# Power.net
KiCad netlist of a schematic drawn in Altium Designer
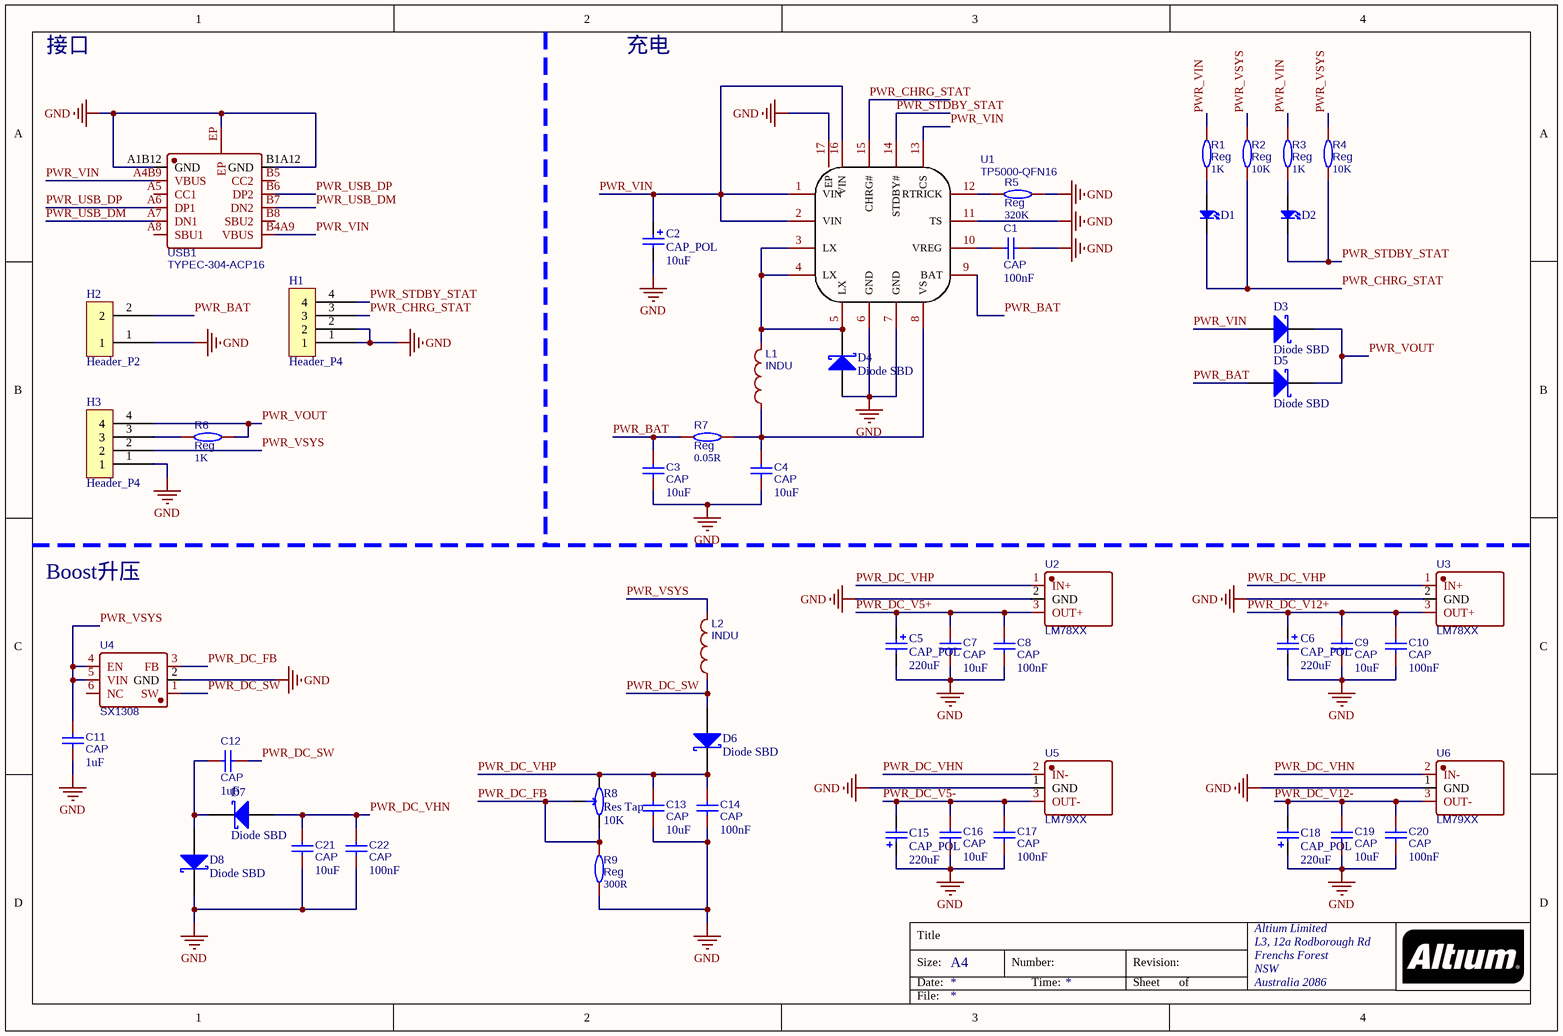
[diagram p0: Power.SchDoc]

(export (version "E")
  (design (tool "Eeschema 10.0.6"))
  (components
    (comp (ref "C1")
      (value "CAP")
      (footprint "C0603")
      (description "Cap")
      (fields
        (field (name "BOM_SUPPLIER PART") "C302008")
        (field (name "BOM_MANUFACTURER PART") "0603B103K101CT")
        (field (name "ALTIUM_VALUE") "100nF")
        (field (name "CONTRIBUTOR") "LCSC")
      )
      (libsource (lib "Levent_lib") (part "CAP"))
    )
    (comp (ref "C2")
      (value "CAP_POL")
      (footprint "CP1206")
      (description "极性电容")
      (fields (field (name "ALTIUM_VALUE") "10uF"))
      (libsource (lib "Levent_lib") (part "CAP_POL"))
    )
    (comp (ref "C3")
      (value "CAP")
      (footprint "C0603")
      (description "Cap")
      (fields
        (field (name "BOM_SUPPLIER PART") "C302008")
        (field (name "BOM_MANUFACTURER PART") "0603B103K101CT")
        (field (name "ALTIUM_VALUE") "10uF")
        (field (name "CONTRIBUTOR") "LCSC")
      )
      (libsource (lib "Levent_lib") (part "CAP"))
    )
    (comp (ref "C4")
      (value "CAP")
      (footprint "C0603")
      (description "Cap")
      (fields
        (field (name "BOM_SUPPLIER PART") "C302008")
        (field (name "BOM_MANUFACTURER PART") "0603B103K101CT")
        (field (name "ALTIUM_VALUE") "10uF")
        (field (name "CONTRIBUTOR") "LCSC")
      )
      (libsource (lib "Levent_lib") (part "CAP"))
    )
    (comp (ref "C5")
      (value "CAP_POL")
      (footprint "CAP_SMD_6.3mm")
      (description "极性电容")
      (fields (field (name "ALTIUM_VALUE") "220uF"))
      (libsource (lib "Levent_lib") (part "CAP_POL"))
    )
    (comp (ref "C6")
      (value "CAP_POL")
      (footprint "CAP_SMD_6.3mm")
      (description "极性电容")
      (fields (field (name "ALTIUM_VALUE") "220uF"))
      (libsource (lib "Levent_lib") (part "CAP_POL"))
    )
    (comp (ref "C7")
      (value "CAP")
      (footprint "C0603")
      (description "Cap")
      (fields
        (field (name "BOM_SUPPLIER PART") "C302008")
        (field (name "BOM_MANUFACTURER PART") "0603B103K101CT")
        (field (name "ALTIUM_VALUE") "10uF")
        (field (name "CONTRIBUTOR") "LCSC")
      )
      (libsource (lib "Levent_lib") (part "CAP"))
    )
    (comp (ref "C8")
      (value "CAP")
      (footprint "C0603")
      (description "Cap")
      (fields
        (field (name "BOM_SUPPLIER PART") "C302008")
        (field (name "BOM_MANUFACTURER PART") "0603B103K101CT")
        (field (name "ALTIUM_VALUE") "100nF")
        (field (name "CONTRIBUTOR") "LCSC")
      )
      (libsource (lib "Levent_lib") (part "CAP"))
    )
    (comp (ref "C9")
      (value "CAP")
      (footprint "C0603")
      (description "Cap")
      (fields
        (field (name "BOM_SUPPLIER PART") "C302008")
        (field (name "BOM_MANUFACTURER PART") "0603B103K101CT")
        (field (name "ALTIUM_VALUE") "10uF")
        (field (name "CONTRIBUTOR") "LCSC")
      )
      (libsource (lib "Levent_lib") (part "CAP"))
    )
    (comp (ref "C10")
      (value "CAP")
      (footprint "C0603")
      (description "Cap")
      (fields
        (field (name "BOM_SUPPLIER PART") "C302008")
        (field (name "BOM_MANUFACTURER PART") "0603B103K101CT")
        (field (name "ALTIUM_VALUE") "100nF")
        (field (name "CONTRIBUTOR") "LCSC")
      )
      (libsource (lib "Levent_lib") (part "CAP"))
    )
    (comp (ref "C11")
      (value "CAP")
      (footprint "C0603")
      (description "Cap")
      (fields
        (field (name "BOM_SUPPLIER PART") "C302008")
        (field (name "BOM_MANUFACTURER PART") "0603B103K101CT")
        (field (name "ALTIUM_VALUE") "1uF")
        (field (name "CONTRIBUTOR") "LCSC")
      )
      (libsource (lib "Levent_lib") (part "CAP"))
    )
    (comp (ref "C12")
      (value "CAP")
      (footprint "C0603")
      (description "Cap")
      (fields
        (field (name "BOM_SUPPLIER PART") "C302008")
        (field (name "BOM_MANUFACTURER PART") "0603B103K101CT")
        (field (name "ALTIUM_VALUE") "1uF")
        (field (name "CONTRIBUTOR") "LCSC")
      )
      (libsource (lib "Levent_lib") (part "CAP"))
    )
    (comp (ref "C13")
      (value "CAP")
      (footprint "C0603")
      (description "Cap")
      (fields
        (field (name "BOM_SUPPLIER PART") "C302008")
        (field (name "BOM_MANUFACTURER PART") "0603B103K101CT")
        (field (name "ALTIUM_VALUE") "10uF")
        (field (name "CONTRIBUTOR") "LCSC")
      )
      (libsource (lib "Levent_lib") (part "CAP"))
    )
    (comp (ref "C14")
      (value "CAP")
      (footprint "C0603")
      (description "Cap")
      (fields
        (field (name "BOM_SUPPLIER PART") "C302008")
        (field (name "BOM_MANUFACTURER PART") "0603B103K101CT")
        (field (name "ALTIUM_VALUE") "100nF")
        (field (name "CONTRIBUTOR") "LCSC")
      )
      (libsource (lib "Levent_lib") (part "CAP"))
    )
    (comp (ref "C15")
      (value "CAP_POL")
      (footprint "CAP_SMD_6.3mm")
      (description "极性电容")
      (fields (field (name "ALTIUM_VALUE") "220uF"))
      (libsource (lib "Levent_lib") (part "CAP_POL"))
    )
    (comp (ref "C16")
      (value "CAP")
      (footprint "C0603")
      (description "Cap")
      (fields
        (field (name "BOM_SUPPLIER PART") "C302008")
        (field (name "BOM_MANUFACTURER PART") "0603B103K101CT")
        (field (name "ALTIUM_VALUE") "10uF")
        (field (name "CONTRIBUTOR") "LCSC")
      )
      (libsource (lib "Levent_lib") (part "CAP"))
    )
    (comp (ref "C17")
      (value "CAP")
      (footprint "C0603")
      (description "Cap")
      (fields
        (field (name "BOM_SUPPLIER PART") "C302008")
        (field (name "BOM_MANUFACTURER PART") "0603B103K101CT")
        (field (name "ALTIUM_VALUE") "100nF")
        (field (name "CONTRIBUTOR") "LCSC")
      )
      (libsource (lib "Levent_lib") (part "CAP"))
    )
    (comp (ref "C18")
      (value "CAP_POL")
      (footprint "CAP_SMD_6.3mm")
      (description "极性电容")
      (fields (field (name "ALTIUM_VALUE") "220uF"))
      (libsource (lib "Levent_lib") (part "CAP_POL"))
    )
    (comp (ref "C19")
      (value "CAP")
      (footprint "C0603")
      (description "Cap")
      (fields
        (field (name "BOM_SUPPLIER PART") "C302008")
        (field (name "BOM_MANUFACTURER PART") "0603B103K101CT")
        (field (name "ALTIUM_VALUE") "10uF")
        (field (name "CONTRIBUTOR") "LCSC")
      )
      (libsource (lib "Levent_lib") (part "CAP"))
    )
    (comp (ref "C20")
      (value "CAP")
      (footprint "C0603")
      (description "Cap")
      (fields
        (field (name "BOM_SUPPLIER PART") "C302008")
        (field (name "BOM_MANUFACTURER PART") "0603B103K101CT")
        (field (name "ALTIUM_VALUE") "100nF")
        (field (name "CONTRIBUTOR") "LCSC")
      )
      (libsource (lib "Levent_lib") (part "CAP"))
    )
    (comp (ref "C21")
      (value "CAP")
      (footprint "C0603")
      (description "Cap")
      (fields
        (field (name "BOM_SUPPLIER PART") "C302008")
        (field (name "BOM_MANUFACTURER PART") "0603B103K101CT")
        (field (name "ALTIUM_VALUE") "10uF")
        (field (name "CONTRIBUTOR") "LCSC")
      )
      (libsource (lib "Levent_lib") (part "CAP"))
    )
    (comp (ref "C22")
      (value "CAP")
      (footprint "C0603")
      (description "Cap")
      (fields
        (field (name "BOM_SUPPLIER PART") "C302008")
        (field (name "BOM_MANUFACTURER PART") "0603B103K101CT")
        (field (name "ALTIUM_VALUE") "100nF")
        (field (name "CONTRIBUTOR") "LCSC")
      )
      (libsource (lib "Levent_lib") (part "CAP"))
    )
    (comp (ref "D1")
      (value "LED")
      (footprint "LED0603_Side")
      (fields (field (name "PUBLISHER") "Altium Limited"))
      (libsource (lib "Levent_lib") (part "LED0"))
    )
    (comp (ref "D2")
      (value "LED")
      (footprint "LED0603_Side")
      (fields (field (name "PUBLISHER") "Altium Limited"))
      (libsource (lib "Levent_lib") (part "LED0"))
    )
    (comp (ref "D3")
      (value "Diode SBD")
      (footprint "SMA_L4.3")
      (description "Schottky Rectifier")
      (fields (field (name "PUBLISHER") "Altium Limited"))
      (libsource (lib "Levent_lib") (part "Diode SBD"))
    )
    (comp (ref "D4")
      (value "Diode SBD")
      (footprint "SMA_L4.3")
      (description "Schottky Rectifier")
      (fields (field (name "PUBLISHER") "Altium Limited"))
      (libsource (lib "Levent_lib") (part "Diode SBD"))
    )
    (comp (ref "D5")
      (value "Diode SBD")
      (footprint "SMA_L4.3")
      (description "Schottky Rectifier")
      (fields (field (name "PUBLISHER") "Altium Limited"))
      (libsource (lib "Levent_lib") (part "Diode SBD"))
    )
    (comp (ref "D6")
      (value "Diode SBD")
      (footprint "SMA_L4.3")
      (description "Schottky Rectifier")
      (fields (field (name "PUBLISHER") "Altium Limited"))
      (libsource (lib "Levent_lib") (part "Diode SBD"))
    )
    (comp (ref "D7")
      (value "Diode SBD")
      (footprint "SMA_L4.3")
      (description "Schottky Rectifier")
      (fields (field (name "PUBLISHER") "Altium Limited"))
      (libsource (lib "Levent_lib") (part "Diode SBD"))
    )
    (comp (ref "D8")
      (value "Diode SBD")
      (footprint "SMA_L4.3")
      (description "Schottky Rectifier")
      (fields (field (name "PUBLISHER") "Altium Limited"))
      (libsource (lib "Levent_lib") (part "Diode SBD"))
    )
    (comp (ref "H1")
      (value "Header_P4")
      (footprint "PH_4Pin")
      (description "4Pin排针")
      (libsource (lib "Levent_lib") (part "Header_P4"))
    )
    (comp (ref "H2")
      (value "Header_P2")
      (footprint "XH_2Pin")
      (description "2Pin排针")
      (libsource (lib "Levent_lib") (part "Header_P2"))
    )
    (comp (ref "H3")
      (value "Header_P4")
      (footprint "PH_4Pin")
      (description "4Pin排针")
      (libsource (lib "Levent_lib") (part "Header_P4"))
    )
    (comp (ref "L1")
      (value "INDU")
      (footprint "SMD_L7.1")
      (description "电感")
      (fields
        (field (name "BOM_SUPPLIER PART") "C182182")
        (field (name "BOM_MANUFACTURER PART") "SLO0630H150MTT")
        (field (name "CONTRIBUTOR") "LCSC")
      )
      (libsource (lib "Levent_lib") (part "IND"))
    )
    (comp (ref "L2")
      (value "INDU")
      (footprint "SMD_L7.1")
      (description "电感")
      (fields
        (field (name "BOM_SUPPLIER PART") "C182182")
        (field (name "BOM_MANUFACTURER PART") "SLO0630H150MTT")
        (field (name "CONTRIBUTOR") "LCSC")
      )
      (libsource (lib "Levent_lib") (part "IND"))
    )
    (comp (ref "R1")
      (value "Reg")
      (footprint "R0603")
      (description "电阻")
      (fields
        (field (name "BOM_SUPPLIER PART") "C465721")
        (field (name "BOM_MANUFACTURER PART") "AR03BTCX1002A")
        (field (name "ALTIUM_VALUE") "1K")
        (field (name "CONTRIBUTOR") "LCSC")
      )
      (libsource (lib "Levent_lib") (part "Res"))
    )
    (comp (ref "R2")
      (value "Reg")
      (footprint "R0603")
      (description "电阻")
      (fields
        (field (name "BOM_SUPPLIER PART") "C465721")
        (field (name "BOM_MANUFACTURER PART") "AR03BTCX1002A")
        (field (name "ALTIUM_VALUE") "10K")
        (field (name "CONTRIBUTOR") "LCSC")
      )
      (libsource (lib "Levent_lib") (part "Res"))
    )
    (comp (ref "R3")
      (value "Reg")
      (footprint "R0603")
      (description "电阻")
      (fields
        (field (name "BOM_SUPPLIER PART") "C465721")
        (field (name "BOM_MANUFACTURER PART") "AR03BTCX1002A")
        (field (name "ALTIUM_VALUE") "1K")
        (field (name "CONTRIBUTOR") "LCSC")
      )
      (libsource (lib "Levent_lib") (part "Res"))
    )
    (comp (ref "R4")
      (value "Reg")
      (footprint "R0603")
      (description "电阻")
      (fields
        (field (name "BOM_SUPPLIER PART") "C465721")
        (field (name "BOM_MANUFACTURER PART") "AR03BTCX1002A")
        (field (name "ALTIUM_VALUE") "10K")
        (field (name "CONTRIBUTOR") "LCSC")
      )
      (libsource (lib "Levent_lib") (part "Res"))
    )
    (comp (ref "R5")
      (value "Reg")
      (footprint "R0603")
      (description "电阻")
      (fields
        (field (name "BOM_SUPPLIER PART") "C465721")
        (field (name "BOM_MANUFACTURER PART") "AR03BTCX1002A")
        (field (name "ALTIUM_VALUE") "320K")
        (field (name "CONTRIBUTOR") "LCSC")
      )
      (libsource (lib "Levent_lib") (part "Res"))
    )
    (comp (ref "R6")
      (value "Reg")
      (footprint "R0603")
      (description "电阻")
      (fields
        (field (name "BOM_SUPPLIER PART") "C465721")
        (field (name "BOM_MANUFACTURER PART") "AR03BTCX1002A")
        (field (name "ALTIUM_VALUE") "1K")
        (field (name "CONTRIBUTOR") "LCSC")
      )
      (libsource (lib "Levent_lib") (part "Res"))
    )
    (comp (ref "R7")
      (value "Reg")
      (footprint "R2512")
      (description "电阻")
      (fields
        (field (name "BOM_SUPPLIER PART") "C465721")
        (field (name "BOM_MANUFACTURER PART") "AR03BTCX1002A")
        (field (name "ALTIUM_VALUE") "0.05R")
        (field (name "CONTRIBUTOR") "LCSC")
      )
      (libsource (lib "Levent_lib") (part "Res"))
    )
    (comp (ref "R8")
      (value "Res Tap")
      (footprint "RES_TAP_HOR")
      (description "可调电阻")
      (fields (field (name "ALTIUM_VALUE") "10K") (field (name "PUBLISHER") "Altium Limited"))
      (libsource (lib "Levent_lib") (part "Res Tap"))
    )
    (comp (ref "R9")
      (value "Reg")
      (footprint "R0603")
      (description "电阻")
      (fields
        (field (name "BOM_SUPPLIER PART") "C465721")
        (field (name "BOM_MANUFACTURER PART") "AR03BTCX1002A")
        (field (name "ALTIUM_VALUE") "300R")
        (field (name "CONTRIBUTOR") "LCSC")
      )
      (libsource (lib "Levent_lib") (part "Res"))
    )
    (comp (ref "U1")
      (value "TP5000-QFN16")
      (footprint "QFN-16_L4.0-W4.0-P0.65-BL-EP2.2")
      (fields (field (name "BOM_SUPPLIER PART") "C51699"))
      (libsource (lib "Levent_lib") (part "TP5000-QFN16"))
    )
    (comp (ref "U2")
      (value "LM78XX")
      (footprint "TO-220-3_2.54_HOR")
      (description "三端稳压(正电压)")
      (fields
        (field (name "BOM_SUPPLIER PART") "C2902509")
        (field (name "BOM_MANUFACTURER PART") "LM7812T")
        (field (name "CONTRIBUTOR") "LCSC")
      )
      (libsource (lib "Levent_lib") (part "LM78XX"))
    )
    (comp (ref "U3")
      (value "LM78XX")
      (footprint "TO-220-3_2.54_HOR")
      (description "三端稳压(正电压)")
      (fields
        (field (name "BOM_SUPPLIER PART") "C2902509")
        (field (name "BOM_MANUFACTURER PART") "LM7812T")
        (field (name "CONTRIBUTOR") "LCSC")
      )
      (libsource (lib "Levent_lib") (part "LM78XX"))
    )
    (comp (ref "U4")
      (value "SX1308")
      (footprint "SOT-23-6")
      (description "升压PWM")
      (fields (field (name "BOM_SUPPLIER PART") "C78162"))
      (libsource (lib "Levent_lib") (part "SX1308"))
    )
    (comp (ref "U5")
      (value "LM79XX")
      (footprint "TO-220-3_2.54_HOR")
      (description "三端稳压(负电压)")
      (fields
        (field (name "BOM_SUPPLIER PART") "C2902509")
        (field (name "BOM_MANUFACTURER PART") "LM7812T")
        (field (name "CONTRIBUTOR") "LCSC")
      )
      (libsource (lib "Levent_lib_commons") (part "LM79XX"))
    )
    (comp (ref "U6")
      (value "LM79XX")
      (footprint "TO-220-3_2.54_HOR")
      (description "三端稳压(负电压)")
      (fields
        (field (name "BOM_SUPPLIER PART") "C2902509")
        (field (name "BOM_MANUFACTURER PART") "LM7812T")
        (field (name "CONTRIBUTOR") "LCSC")
      )
      (libsource (lib "Levent_lib_commons") (part "LM79XX"))
    )
    (comp (ref "USB1")
      (value "TYPEC-304-ACP16")
      (footprint "USB-C-SMD_TYPE-C-16P")
      (description "全引脚USB TYPEC母座")
      (fields (field (name "BOM_SUPPLIER PART") "C2982555") (field (name "CONTRIBUTOR") "LCSC"))
      (libsource (lib "Levent_lib") (part "USB_TYPEC_12P"))
    )
  )
  (nets
    (net (code "1") (name "/PWR_BAT") (class "Default")
      (node (ref "C3") (pin "1") (pinfunction "1_1") (pintype "passive"))
      (node (ref "D5") (pin "2") (pinfunction "A_2") (pintype "passive"))
      (node (ref "H2") (pin "2") (pinfunction "2_2") (pintype "passive"))
      (node (ref "R7") (pin "1") (pinfunction "1_1") (pintype "passive"))
      (node (ref "U1") (pin "9") (pinfunction "BAT_9") (pintype "passive"))
    )
    (net (code "2") (name "/PWR_CHRG_STAT") (class "Default")
      (node (ref "D1") (pin "1") (pinfunction "K_1") (pintype "passive"))
      (node (ref "H1") (pin "3") (pinfunction "3_3") (pintype "passive"))
      (node (ref "R2") (pin "1") (pinfunction "1_1") (pintype "passive"))
      (node (ref "U1") (pin "15") (pinfunction "CHRG#_15") (pintype "passive"))
    )
    (net (code "3") (name "/PWR_DC_FB") (class "Default")
      (node (ref "R8") (pin "1") (pinfunction "A_1") (pintype "passive"))
      (node (ref "R8") (pin "3") (pinfunction "TAP_3") (pintype "passive"))
      (node (ref "R9") (pin "2") (pinfunction "2_2") (pintype "passive"))
      (node (ref "U4") (pin "3") (pinfunction "FB_3") (pintype "passive"))
    )
    (net (code "4") (name "/PWR_DC_SW") (class "Default")
      (node (ref "C12") (pin "1") (pinfunction "1_1") (pintype "passive"))
      (node (ref "D6") (pin "2") (pinfunction "A_2") (pintype "passive"))
      (node (ref "L2") (pin "1") (pinfunction "1_1") (pintype "passive"))
      (node (ref "U4") (pin "1") (pinfunction "SW_1") (pintype "passive"))
    )
    (net (code "5") (name "/PWR_DC_V5+") (class "Default")
      (node (ref "C5") (pin "1") (pinfunction "1_1") (pintype "passive"))
      (node (ref "C7") (pin "1") (pinfunction "1_1") (pintype "passive"))
      (node (ref "C8") (pin "1") (pinfunction "1_1") (pintype "passive"))
      (node (ref "U2") (pin "3") (pinfunction "OUT+_3") (pintype "passive"))
    )
    (net (code "6") (name "/PWR_DC_V5-") (class "Default")
      (node (ref "C15") (pin "2") (pinfunction "2_2") (pintype "passive"))
      (node (ref "C16") (pin "1") (pinfunction "1_1") (pintype "passive"))
      (node (ref "C17") (pin "1") (pinfunction "1_1") (pintype "passive"))
      (node (ref "U5") (pin "3") (pinfunction "OUT-_3") (pintype "passive"))
    )
    (net (code "7") (name "/PWR_DC_V12+") (class "Default")
      (node (ref "C10") (pin "1") (pinfunction "1_1") (pintype "passive"))
      (node (ref "C6") (pin "1") (pinfunction "1_1") (pintype "passive"))
      (node (ref "C9") (pin "1") (pinfunction "1_1") (pintype "passive"))
      (node (ref "U3") (pin "3") (pinfunction "OUT+_3") (pintype "passive"))
    )
    (net (code "8") (name "/PWR_DC_V12-") (class "Default")
      (node (ref "C18") (pin "2") (pinfunction "2_2") (pintype "passive"))
      (node (ref "C19") (pin "1") (pinfunction "1_1") (pintype "passive"))
      (node (ref "C20") (pin "1") (pinfunction "1_1") (pintype "passive"))
      (node (ref "U6") (pin "3") (pinfunction "OUT-_3") (pintype "passive"))
    )
    (net (code "9") (name "/PWR_DC_VHN") (class "Default")
      (node (ref "C21") (pin "1") (pinfunction "1_1") (pintype "passive"))
      (node (ref "C22") (pin "1") (pinfunction "1_1") (pintype "passive"))
      (node (ref "D7") (pin "2") (pinfunction "A_2") (pintype "passive"))
      (node (ref "U5") (pin "2") (pinfunction "IN-_2") (pintype "passive"))
      (node (ref "U6") (pin "2") (pinfunction "IN-_2") (pintype "passive"))
    )
    (net (code "10") (name "/PWR_DC_VHP") (class "Default")
      (node (ref "C13") (pin "1") (pinfunction "1_1") (pintype "passive"))
      (node (ref "C14") (pin "1") (pinfunction "1_1") (pintype "passive"))
      (node (ref "D6") (pin "1") (pinfunction "K_1") (pintype "passive"))
      (node (ref "R8") (pin "2") (pinfunction "B_2") (pintype "passive"))
      (node (ref "U2") (pin "1") (pinfunction "IN+_1") (pintype "passive"))
      (node (ref "U3") (pin "1") (pinfunction "IN+_1") (pintype "passive"))
    )
    (net (code "11") (name "/PWR_STDBY_STAT") (class "Default")
      (node (ref "D2") (pin "1") (pinfunction "K_1") (pintype "passive"))
      (node (ref "H1") (pin "4") (pinfunction "4_4") (pintype "passive"))
      (node (ref "R4") (pin "1") (pinfunction "1_1") (pintype "passive"))
      (node (ref "U1") (pin "14") (pinfunction "STDBY#_14") (pintype "passive"))
    )
    (net (code "12") (name "/PWR_USB_DM") (class "Default")
      (node (ref "USB1") (pin "A7") (pinfunction "DN1_A7") (pintype "passive"))
      (node (ref "USB1") (pin "B7") (pinfunction "DN2_B7") (pintype "passive"))
    )
    (net (code "13") (name "/PWR_USB_DP") (class "Default")
      (node (ref "USB1") (pin "A6") (pinfunction "DP1_A6") (pintype "passive"))
      (node (ref "USB1") (pin "B6") (pinfunction "DP2_B6") (pintype "passive"))
    )
    (net (code "14") (name "/PWR_VIN") (class "Default")
      (node (ref "C2") (pin "1") (pinfunction "1_1") (pintype "passive"))
      (node (ref "D3") (pin "2") (pinfunction "A_2") (pintype "passive"))
      (node (ref "R1") (pin "2") (pinfunction "2_2") (pintype "passive"))
      (node (ref "R3") (pin "2") (pinfunction "2_2") (pintype "passive"))
      (node (ref "U1") (pin "1") (pinfunction "VIN_1") (pintype "passive"))
      (node (ref "U1") (pin "13") (pinfunction "CS_13") (pintype "passive"))
      (node (ref "U1") (pin "16") (pinfunction "VIN_16") (pintype "passive"))
      (node (ref "U1") (pin "2") (pinfunction "VIN_2") (pintype "passive"))
      (node (ref "USB1") (pin "A4B9") (pinfunction "VBUS_A4B9") (pintype "passive"))
      (node (ref "USB1") (pin "B4A9") (pinfunction "VBUS_B4A9") (pintype "passive"))
    )
    (net (code "15") (name "/PWR_VOUT") (class "Default")
      (node (ref "D3") (pin "1") (pinfunction "K_1") (pintype "passive"))
      (node (ref "D5") (pin "1") (pinfunction "K_1") (pintype "passive"))
      (node (ref "H3") (pin "4") (pinfunction "4_4") (pintype "passive"))
      (node (ref "R6") (pin "1") (pinfunction "1_1") (pintype "passive"))
    )
    (net (code "16") (name "/PWR_VSYS") (class "Default")
      (node (ref "C11") (pin "1") (pinfunction "1_1") (pintype "passive"))
      (node (ref "H3") (pin "2") (pinfunction "2_2") (pintype "passive"))
      (node (ref "L2") (pin "2") (pinfunction "2_2") (pintype "passive"))
      (node (ref "R2") (pin "2") (pinfunction "2_2") (pintype "passive"))
      (node (ref "R4") (pin "2") (pinfunction "2_2") (pintype "passive"))
      (node (ref "U4") (pin "4") (pinfunction "EN_4") (pintype "passive"))
      (node (ref "U4") (pin "5") (pinfunction "VIN_5") (pintype "passive"))
    )
    (net (code "17") (name "GND") (class "Default")
      (node (ref "C1") (pin "2") (pinfunction "2_2") (pintype "passive"))
      (node (ref "C10") (pin "2") (pinfunction "2_2") (pintype "passive"))
      (node (ref "C11") (pin "2") (pinfunction "2_2") (pintype "passive"))
      (node (ref "C13") (pin "2") (pinfunction "2_2") (pintype "passive"))
      (node (ref "C14") (pin "2") (pinfunction "2_2") (pintype "passive"))
      (node (ref "C15") (pin "1") (pinfunction "1_1") (pintype "passive"))
      (node (ref "C16") (pin "2") (pinfunction "2_2") (pintype "passive"))
      (node (ref "C17") (pin "2") (pinfunction "2_2") (pintype "passive"))
      (node (ref "C18") (pin "1") (pinfunction "1_1") (pintype "passive"))
      (node (ref "C19") (pin "2") (pinfunction "2_2") (pintype "passive"))
      (node (ref "C2") (pin "2") (pinfunction "2_2") (pintype "passive"))
      (node (ref "C20") (pin "2") (pinfunction "2_2") (pintype "passive"))
      (node (ref "C21") (pin "2") (pinfunction "2_2") (pintype "passive"))
      (node (ref "C22") (pin "2") (pinfunction "2_2") (pintype "passive"))
      (node (ref "C3") (pin "2") (pinfunction "2_2") (pintype "passive"))
      (node (ref "C4") (pin "2") (pinfunction "2_2") (pintype "passive"))
      (node (ref "C5") (pin "2") (pinfunction "2_2") (pintype "passive"))
      (node (ref "C6") (pin "2") (pinfunction "2_2") (pintype "passive"))
      (node (ref "C7") (pin "2") (pinfunction "2_2") (pintype "passive"))
      (node (ref "C8") (pin "2") (pinfunction "2_2") (pintype "passive"))
      (node (ref "C9") (pin "2") (pinfunction "2_2") (pintype "passive"))
      (node (ref "D4") (pin "2") (pinfunction "A_2") (pintype "passive"))
      (node (ref "D8") (pin "1") (pinfunction "K_1") (pintype "passive"))
      (node (ref "H1") (pin "1") (pinfunction "1_1") (pintype "passive"))
      (node (ref "H1") (pin "2") (pinfunction "2_2") (pintype "passive"))
      (node (ref "H2") (pin "1") (pinfunction "1_1") (pintype "passive"))
      (node (ref "H3") (pin "1") (pinfunction "1_1") (pintype "passive"))
      (node (ref "R5") (pin "2") (pinfunction "2_2") (pintype "passive"))
      (node (ref "R9") (pin "1") (pinfunction "1_1") (pintype "passive"))
      (node (ref "U1") (pin "11") (pinfunction "TS_11") (pintype "passive"))
      (node (ref "U1") (pin "17") (pinfunction "EP_17") (pintype "passive"))
      (node (ref "U1") (pin "6") (pinfunction "GND_6") (pintype "passive"))
      (node (ref "U1") (pin "7") (pinfunction "GND_7") (pintype "passive"))
      (node (ref "U2") (pin "2") (pinfunction "GND_2") (pintype "passive"))
      (node (ref "U3") (pin "2") (pinfunction "GND_2") (pintype "passive"))
      (node (ref "U4") (pin "2") (pinfunction "GND_2") (pintype "passive"))
      (node (ref "U5") (pin "1") (pinfunction "GND_1") (pintype "passive"))
      (node (ref "U6") (pin "1") (pinfunction "GND_1") (pintype "passive"))
      (node (ref "USB1") (pin "A1B12") (pinfunction "GND_A1B12") (pintype "passive"))
      (node (ref "USB1") (pin "B1A12") (pinfunction "GND_B1A12") (pintype "passive"))
      (node (ref "USB1") (pin "EP") (pinfunction "EP_EP") (pintype "passive"))
    )
    (net (code "18") (name "Net-(D1-A)") (class "Default")
      (node (ref "D1") (pin "2") (pinfunction "A_2") (pintype "passive"))
      (node (ref "R1") (pin "1") (pinfunction "1_1") (pintype "passive"))
    )
    (net (code "19") (name "Net-(D2-A)") (class "Default")
      (node (ref "D2") (pin "2") (pinfunction "A_2") (pintype "passive"))
      (node (ref "R3") (pin "1") (pinfunction "1_1") (pintype "passive"))
    )
    (net (code "20") (name "Net-(D4-K)") (class "Default")
      (node (ref "D4") (pin "1") (pinfunction "K_1") (pintype "passive"))
      (node (ref "L1") (pin "2") (pinfunction "2_2") (pintype "passive"))
      (node (ref "U1") (pin "3") (pinfunction "LX_3") (pintype "passive"))
      (node (ref "U1") (pin "4") (pinfunction "LX_4") (pintype "passive"))
      (node (ref "U1") (pin "5") (pinfunction "LX_5") (pintype "passive"))
    )
    (net (code "21") (name "Net-(D7-K)") (class "Default")
      (node (ref "C12") (pin "2") (pinfunction "2_2") (pintype "passive"))
      (node (ref "D7") (pin "1") (pinfunction "K_1") (pintype "passive"))
      (node (ref "D8") (pin "2") (pinfunction "A_2") (pintype "passive"))
    )
    (net (code "22") (name "Net-(H3-Pad3)") (class "Default")
      (node (ref "H3") (pin "3") (pinfunction "3_3") (pintype "passive"))
      (node (ref "R6") (pin "2") (pinfunction "2_2") (pintype "passive"))
    )
    (net (code "23") (name "Net-(U1-RTRICK)") (class "Default")
      (node (ref "R5") (pin "1") (pinfunction "1_1") (pintype "passive"))
      (node (ref "U1") (pin "12") (pinfunction "RTRICK_12") (pintype "passive"))
    )
    (net (code "24") (name "Net-(U1-VREG)") (class "Default")
      (node (ref "C1") (pin "1") (pinfunction "1_1") (pintype "passive"))
      (node (ref "U1") (pin "10") (pinfunction "VREG_10") (pintype "passive"))
    )
    (net (code "25") (name "Net-(U1-VS)") (class "Default")
      (node (ref "C4") (pin "1") (pinfunction "1_1") (pintype "passive"))
      (node (ref "L1") (pin "1") (pinfunction "1_1") (pintype "passive"))
      (node (ref "R7") (pin "2") (pinfunction "2_2") (pintype "passive"))
      (node (ref "U1") (pin "8") (pinfunction "VS_8") (pintype "passive"))
    )
    (net (code "26") (name "unconnected-(U4-NC-Pad6)") (class "Default")
      (node (ref "U4") (pin "6") (pinfunction "NC_6") (pintype "passive"))
    )
    (net (code "27") (name "unconnected-(USB1-CC1-PadA5)") (class "Default")
      (node (ref "USB1") (pin "A5") (pinfunction "CC1_A5") (pintype "passive"))
    )
    (net (code "28") (name "unconnected-(USB1-CC2-PadB5)") (class "Default")
      (node (ref "USB1") (pin "B5") (pinfunction "CC2_B5") (pintype "passive"))
    )
    (net (code "29") (name "unconnected-(USB1-SBU1-PadA8)") (class "Default")
      (node (ref "USB1") (pin "A8") (pinfunction "SBU1_A8") (pintype "passive"))
    )
    (net (code "30") (name "unconnected-(USB1-SBU2-PadB8)") (class "Default")
      (node (ref "USB1") (pin "B8") (pinfunction "SBU2_B8") (pintype "passive"))
    )
  )
)
